# 24V_Multiphase_Buck.net
KiCad netlist of a schematic drawn in Altium Designer
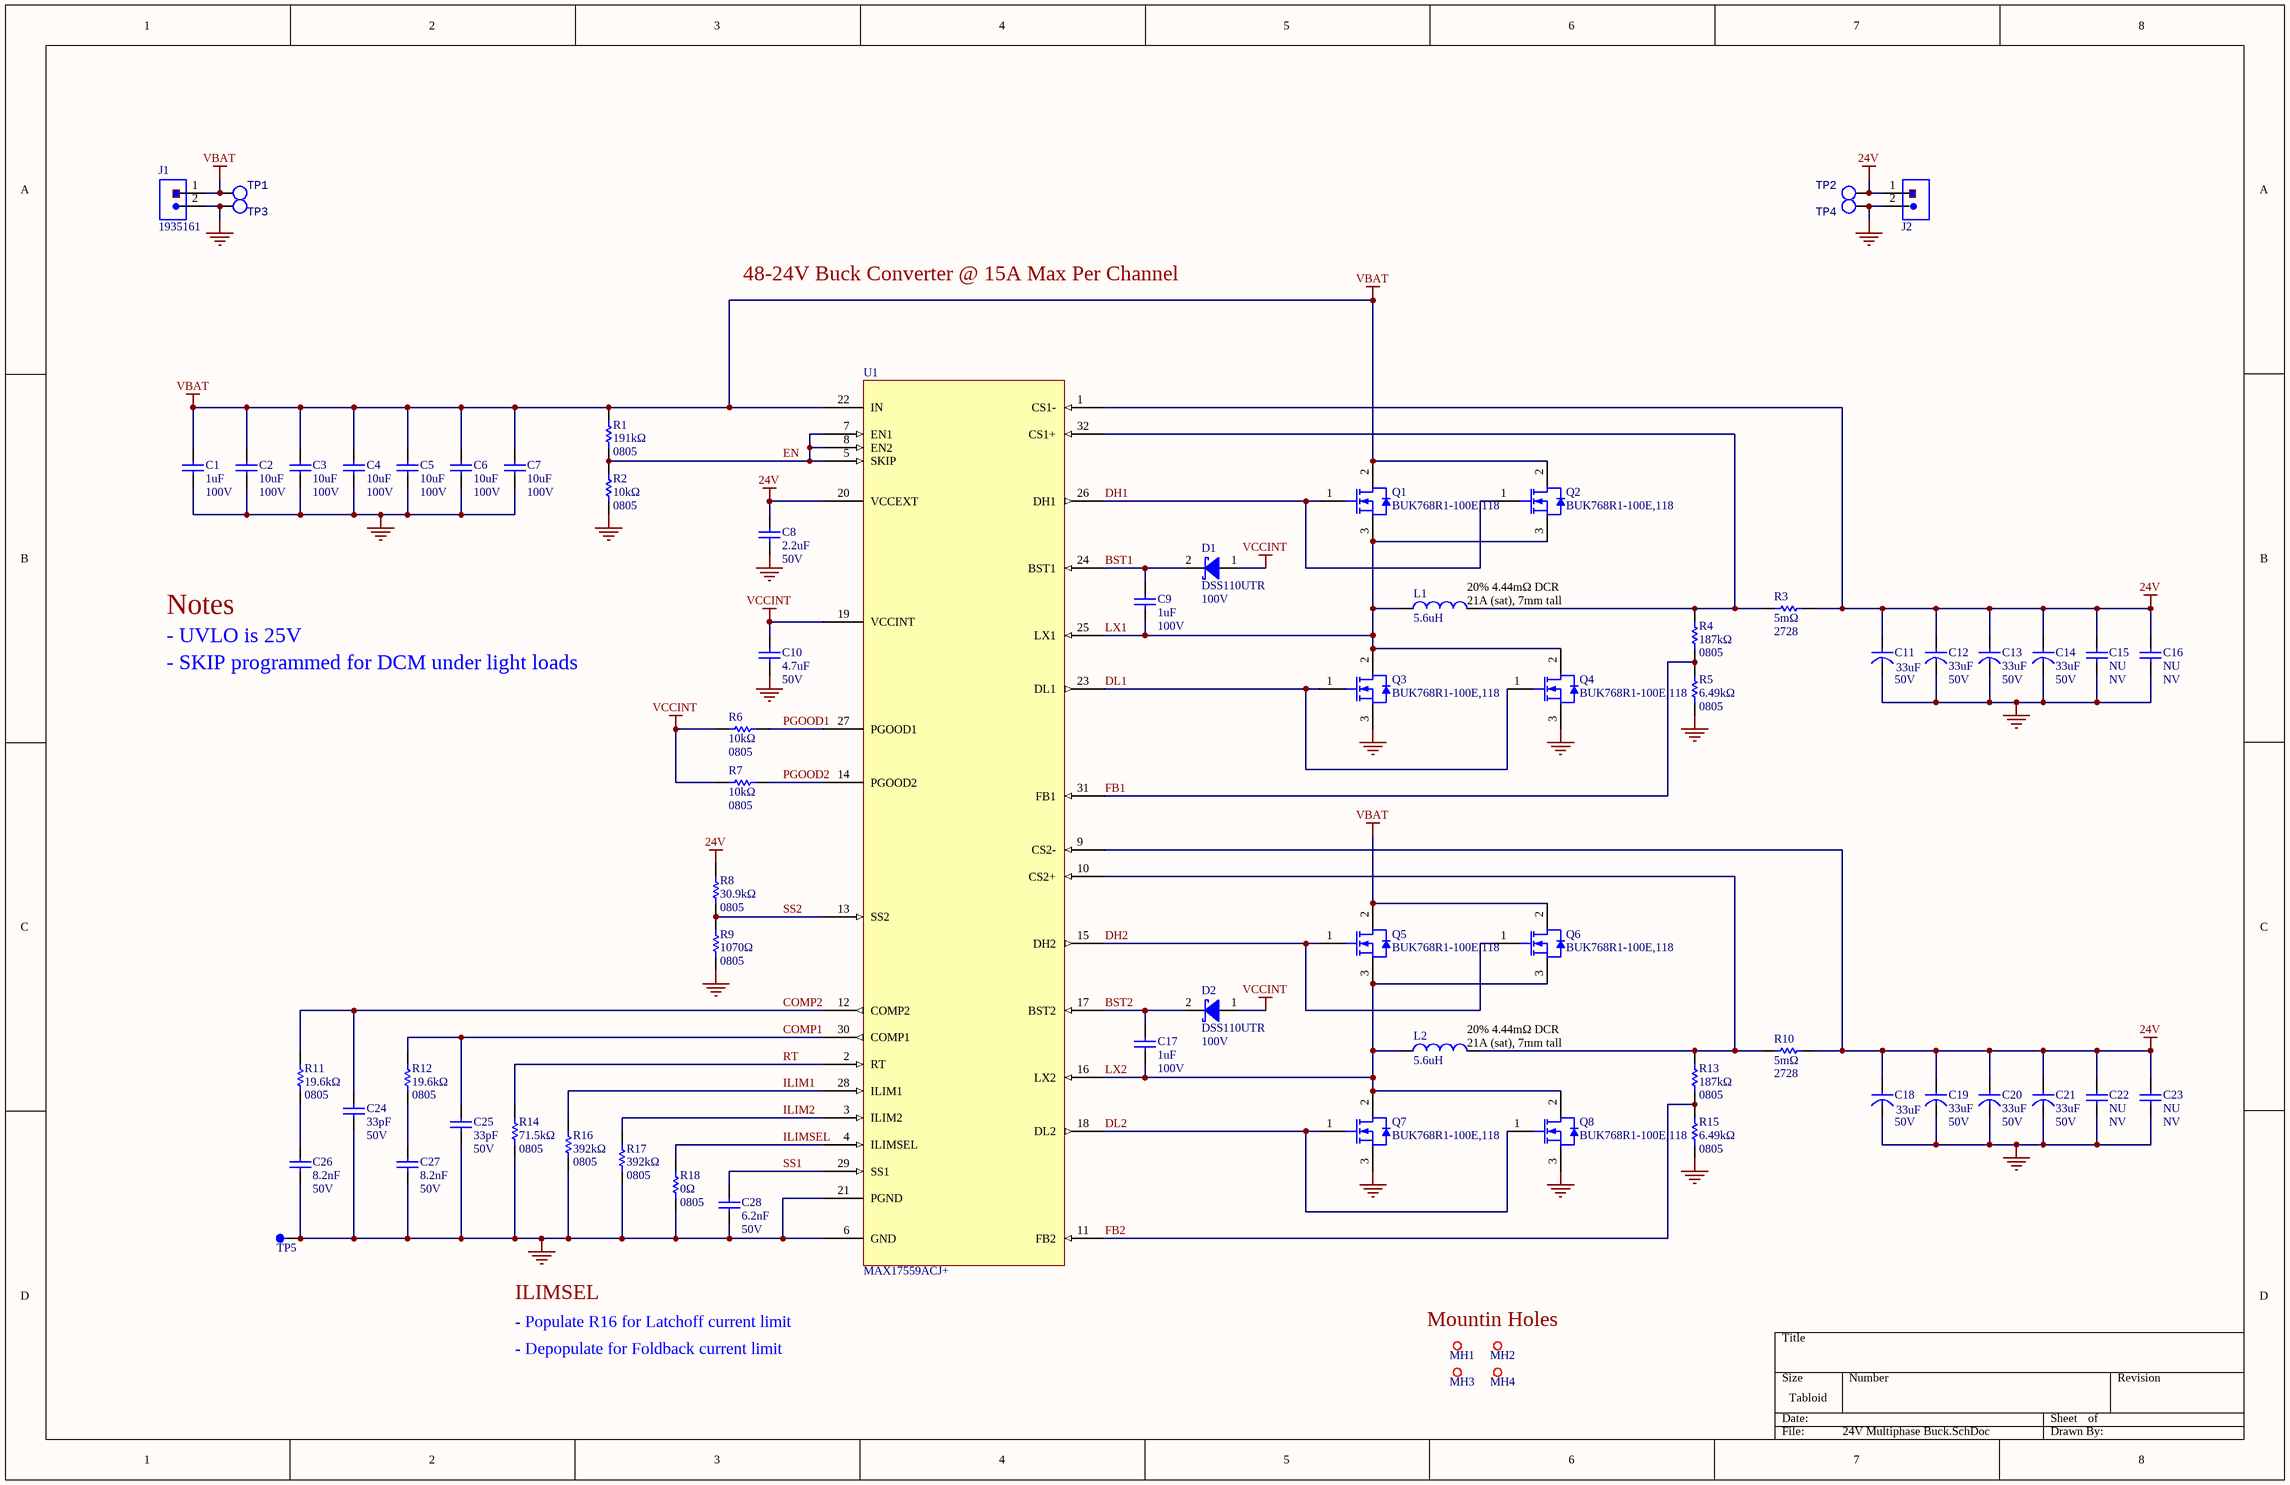
[diagram p0: 24V Multiphase Buck.SchDoc]

(export (version "E")
  (design (tool "Eeschema 10.0.6"))
  (components
    (comp (ref "C1")
      (value "1uF")
      (footprint "C1206")
      (fields
        (field (name "VOLTAGE") "100V")
        (field (name "PART NUMBER") "CL31B105KCHNFNE")
        (field (name "MANUFACTURER") "Samsung Electro-Mechanics")
        (field (name "Comment") "Ceramic Cap")
      )
      (libsource (lib "altium-db-library") (part "Ceramic Cap"))
    )
    (comp (ref "C2")
      (value "10uF")
      (footprint "C2220")
      (fields
        (field (name "VOLTAGE") "100V")
        (field (name "PART NUMBER") "22201C106KAT2A")
        (field (name "MANUFACTURER") "KYOCERA AVX")
        (field (name "Comment") "Ceramic Cap")
      )
      (libsource (lib "altium-db-library") (part "Ceramic Cap"))
    )
    (comp (ref "C3")
      (value "10uF")
      (footprint "C2220")
      (fields
        (field (name "VOLTAGE") "100V")
        (field (name "PART NUMBER") "22201C106KAT2A")
        (field (name "MANUFACTURER") "KYOCERA AVX")
        (field (name "Comment") "Ceramic Cap")
      )
      (libsource (lib "altium-db-library") (part "Ceramic Cap"))
    )
    (comp (ref "C4")
      (value "10uF")
      (footprint "C2220")
      (fields
        (field (name "VOLTAGE") "100V")
        (field (name "PART NUMBER") "22201C106KAT2A")
        (field (name "MANUFACTURER") "KYOCERA AVX")
        (field (name "Comment") "Ceramic Cap")
      )
      (libsource (lib "altium-db-library") (part "Ceramic Cap"))
    )
    (comp (ref "C5")
      (value "10uF")
      (footprint "C2220")
      (fields
        (field (name "VOLTAGE") "100V")
        (field (name "PART NUMBER") "22201C106KAT2A")
        (field (name "MANUFACTURER") "KYOCERA AVX")
        (field (name "Comment") "Ceramic Cap")
      )
      (libsource (lib "altium-db-library") (part "Ceramic Cap"))
    )
    (comp (ref "C6")
      (value "10uF")
      (footprint "C2220")
      (fields
        (field (name "VOLTAGE") "100V")
        (field (name "PART NUMBER") "22201C106KAT2A")
        (field (name "MANUFACTURER") "KYOCERA AVX")
        (field (name "Comment") "Ceramic Cap")
      )
      (libsource (lib "altium-db-library") (part "Ceramic Cap"))
    )
    (comp (ref "C7")
      (value "10uF")
      (footprint "C2220")
      (fields
        (field (name "VOLTAGE") "100V")
        (field (name "PART NUMBER") "22201C106KAT2A")
        (field (name "MANUFACTURER") "KYOCERA AVX")
        (field (name "Comment") "Ceramic Cap")
      )
      (libsource (lib "altium-db-library") (part "Ceramic Cap"))
    )
    (comp (ref "C8")
      (value "2.2uF")
      (footprint "C0805")
      (fields
        (field (name "VOLTAGE") "50V")
        (field (name "PART NUMBER") "CL21A225KBFNNNE")
        (field (name "MANUFACTURER") "Samsung Electro-Mechanics")
        (field (name "Comment") "Ceramic Cap")
      )
      (libsource (lib "altium-db-library") (part "Ceramic Cap"))
    )
    (comp (ref "C9")
      (value "1uF")
      (footprint "C1206")
      (fields
        (field (name "VOLTAGE") "100V")
        (field (name "PART NUMBER") "CL31B105KCHNFNE")
        (field (name "MANUFACTURER") "Samsung Electro-Mechanics")
        (field (name "Comment") "Ceramic Cap")
      )
      (libsource (lib "altium-db-library") (part "Ceramic Cap"))
    )
    (comp (ref "C10")
      (value "4.7uF")
      (footprint "C0805")
      (fields
        (field (name "VOLTAGE") "50V")
        (field (name "PART NUMBER") "GRM21BR61H475KE51L")
        (field (name "MANUFACTURER") "Murata Electronics")
        (field (name "Comment") "Ceramic Cap")
      )
      (libsource (lib "altium-db-library") (part "Ceramic Cap"))
    )
    (comp (ref "C11")
      (value "33uF")
      (footprint "CAPAE9983X105M")
      (fields
        (field (name "VOLTAGE") "50V")
        (field (name "PART NUMBER") "EEV-FC1H330P")
        (field (name "MANUFACTURER") "Panasonic Electronic Components")
        (field (name "Comment") "Electro Cap")
      )
      (libsource (lib "altium-db-library") (part "Electro Cap"))
    )
    (comp (ref "C12")
      (value "33uF")
      (footprint "CAPAE9983X105M")
      (fields
        (field (name "VOLTAGE") "50V")
        (field (name "PART NUMBER") "EEV-FC1H330P")
        (field (name "MANUFACTURER") "Panasonic Electronic Components")
        (field (name "Comment") "Electro Cap")
      )
      (libsource (lib "altium-db-library") (part "Electro Cap"))
    )
    (comp (ref "C13")
      (value "33uF")
      (footprint "CAPAE9983X105M")
      (fields
        (field (name "VOLTAGE") "50V")
        (field (name "PART NUMBER") "EEV-FC1H330P")
        (field (name "MANUFACTURER") "Panasonic Electronic Components")
        (field (name "Comment") "Electro Cap")
      )
      (libsource (lib "altium-db-library") (part "Electro Cap"))
    )
    (comp (ref "C14")
      (value "33uF")
      (footprint "CAPAE9983X105M")
      (fields
        (field (name "VOLTAGE") "50V")
        (field (name "PART NUMBER") "EEV-FC1H330P")
        (field (name "MANUFACTURER") "Panasonic Electronic Components")
        (field (name "Comment") "Electro Cap")
      )
      (libsource (lib "altium-db-library") (part "Electro Cap"))
    )
    (comp (ref "C15")
      (value "NU")
      (footprint "CAPC6153X67N")
      (fields
        (field (name "VOLTAGE") "NV")
        (field (name "PART NUMBER") "KRM55WR71H336MH01K")
        (field (name "MANUFACTURER") "Murata Electronics")
        (field (name "Comment") "Ceramic Cap")
      )
      (libsource (lib "altium-db-library") (part "Ceramic Cap"))
    )
    (comp (ref "C16")
      (value "NU")
      (footprint "CAPC6153X67N")
      (fields
        (field (name "VOLTAGE") "NV")
        (field (name "PART NUMBER") "KRM55WR71H336MH01K")
        (field (name "MANUFACTURER") "Murata Electronics")
        (field (name "Comment") "Ceramic Cap")
      )
      (libsource (lib "altium-db-library") (part "Ceramic Cap"))
    )
    (comp (ref "C17")
      (value "1uF")
      (footprint "C1206")
      (fields
        (field (name "VOLTAGE") "100V")
        (field (name "PART NUMBER") "CL31B105KCHNFNE")
        (field (name "MANUFACTURER") "Samsung Electro-Mechanics")
        (field (name "Comment") "Ceramic Cap")
      )
      (libsource (lib "altium-db-library") (part "Ceramic Cap"))
    )
    (comp (ref "C18")
      (value "33uF")
      (footprint "CAPAE9983X105M")
      (fields
        (field (name "VOLTAGE") "50V")
        (field (name "PART NUMBER") "EEV-FC1H330P")
        (field (name "MANUFACTURER") "Panasonic Electronic Components")
        (field (name "Comment") "Electro Cap")
      )
      (libsource (lib "altium-db-library") (part "Electro Cap"))
    )
    (comp (ref "C19")
      (value "33uF")
      (footprint "CAPAE9983X105M")
      (fields
        (field (name "VOLTAGE") "50V")
        (field (name "PART NUMBER") "EEV-FC1H330P")
        (field (name "MANUFACTURER") "Panasonic Electronic Components")
        (field (name "Comment") "Electro Cap")
      )
      (libsource (lib "altium-db-library") (part "Electro Cap"))
    )
    (comp (ref "C20")
      (value "33uF")
      (footprint "CAPAE9983X105M")
      (fields
        (field (name "VOLTAGE") "50V")
        (field (name "PART NUMBER") "EEV-FC1H330P")
        (field (name "MANUFACTURER") "Panasonic Electronic Components")
        (field (name "Comment") "Electro Cap")
      )
      (libsource (lib "altium-db-library") (part "Electro Cap"))
    )
    (comp (ref "C21")
      (value "33uF")
      (footprint "CAPAE9983X105M")
      (fields
        (field (name "VOLTAGE") "50V")
        (field (name "PART NUMBER") "EEV-FC1H330P")
        (field (name "MANUFACTURER") "Panasonic Electronic Components")
        (field (name "Comment") "Electro Cap")
      )
      (libsource (lib "altium-db-library") (part "Electro Cap"))
    )
    (comp (ref "C22")
      (value "NU")
      (footprint "CAPC6153X67N")
      (fields
        (field (name "VOLTAGE") "NV")
        (field (name "PART NUMBER") "KRM55WR71H336MH01K")
        (field (name "MANUFACTURER") "Murata Electronics")
        (field (name "Comment") "Ceramic Cap")
      )
      (libsource (lib "altium-db-library") (part "Ceramic Cap"))
    )
    (comp (ref "C23")
      (value "NU")
      (footprint "CAPC6153X67N")
      (fields
        (field (name "VOLTAGE") "NV")
        (field (name "PART NUMBER") "KRM55WR71H336MH01K")
        (field (name "MANUFACTURER") "Murata Electronics")
        (field (name "Comment") "Ceramic Cap")
      )
      (libsource (lib "altium-db-library") (part "Ceramic Cap"))
    )
    (comp (ref "C24")
      (value "33pF")
      (footprint "C0805")
      (fields
        (field (name "VOLTAGE") "50V")
        (field (name "PART NUMBER") "C0805C330K5GAC7800")
        (field (name "MANUFACTURER") "KEMET")
        (field (name "Comment") "Ceramic Cap")
      )
      (libsource (lib "altium-db-library") (part "Ceramic Cap"))
    )
    (comp (ref "C25")
      (value "33pF")
      (footprint "C0805")
      (fields
        (field (name "VOLTAGE") "50V")
        (field (name "PART NUMBER") "C0805C330K5GAC7800")
        (field (name "MANUFACTURER") "KEMET")
        (field (name "Comment") "Ceramic Cap")
      )
      (libsource (lib "altium-db-library") (part "Ceramic Cap"))
    )
    (comp (ref "C26")
      (value "8.2nF")
      (footprint "C0805")
      (fields
        (field (name "VOLTAGE") "50V")
        (field (name "PART NUMBER") "CC0805KRX7R9BB822")
        (field (name "MANUFACTURER") "YAGEO")
        (field (name "Comment") "Ceramic Cap")
      )
      (libsource (lib "altium-db-library") (part "Ceramic Cap"))
    )
    (comp (ref "C27")
      (value "8.2nF")
      (footprint "C0805")
      (fields
        (field (name "VOLTAGE") "50V")
        (field (name "PART NUMBER") "CC0805KRX7R9BB822")
        (field (name "MANUFACTURER") "YAGEO")
        (field (name "Comment") "Ceramic Cap")
      )
      (libsource (lib "altium-db-library") (part "Ceramic Cap"))
    )
    (comp (ref "C28")
      (value "6.2nF")
      (footprint "C0805")
      (fields
        (field (name "VOLTAGE") "50V")
        (field (name "PART NUMBER") "GRM2195C1H622JA01D")
        (field (name "MANUFACTURER") "Murata Electronics")
        (field (name "Comment") "Ceramic Cap")
      )
      (libsource (lib "altium-db-library") (part "Ceramic Cap"))
    )
    (comp (ref "D1")
      (value "Schottky Diode")
      (footprint "SODFL360X110-2N")
      (fields
        (field (name "MANUFACTURER PART NUMBER") "DSS110UTR")
        (field (name "VR") "100V")
        (field (name "PART NUMBER") "DSS110UTR")
      )
      (libsource (lib "altium-db-library") (part "Schottky Diode"))
    )
    (comp (ref "D2")
      (value "Schottky Diode")
      (footprint "SODFL360X110-2N")
      (fields
        (field (name "MANUFACTURER PART NUMBER") "DSS110UTR")
        (field (name "VR") "100V")
        (field (name "PART NUMBER") "DSS110UTR")
      )
      (libsource (lib "altium-db-library") (part "Schottky Diode"))
    )
    (comp (ref "J1")
      (value "1935161")
      (footprint "1935161")
      (description "2 Port Terminal")
      (fields (field (name "MANUFACTURER") "Phoenix Contact"))
      (libsource (lib "") (part "1935161_1"))
    )
    (comp (ref "J2")
      (value "1935161")
      (footprint "1935161")
      (fields (field (name "MANUFACTURER") "Phoenix Contact"))
      (libsource (lib "altium-db-library") (part "1935161"))
    )
    (comp (ref "L1")
      (value "5.6uH")
      (footprint "IHLP6767GZER5R6M11")
      (fields
        (field (name "PART NUMBER") "IHLP6767GZER5R6M11")
        (field (name "MANUFACTURER") "Vishay Dale")
        (field (name "TOLERANCE") "20%")
      )
      (libsource (lib "altium-db-library") (part "Inductor"))
    )
    (comp (ref "L2")
      (value "5.6uH")
      (footprint "IHLP6767GZER5R6M11")
      (fields
        (field (name "PART NUMBER") "IHLP6767GZER5R6M11")
        (field (name "MANUFACTURER") "Vishay Dale")
        (field (name "TOLERANCE") "20%")
      )
      (libsource (lib "altium-db-library") (part "Inductor"))
    )
    (comp (ref "MH1")
      (value "MOUNTING_HOLE_M3")
      (footprint "MOUNTING_HOLE_3mm")
      (libsource (lib "UWRT_Schematic_Library_2020") (part "MOUNTING_HOLE_M3"))
    )
    (comp (ref "MH2")
      (value "MOUNTING_HOLE_M3")
      (footprint "MOUNTING_HOLE_3mm")
      (libsource (lib "UWRT_Schematic_Library_2020") (part "MOUNTING_HOLE_M3"))
    )
    (comp (ref "MH3")
      (value "MOUNTING_HOLE_M3")
      (footprint "MOUNTING_HOLE_3mm")
      (libsource (lib "UWRT_Schematic_Library_2020") (part "MOUNTING_HOLE_M3"))
    )
    (comp (ref "MH4")
      (value "MOUNTING_HOLE_M3")
      (footprint "MOUNTING_HOLE_3mm")
      (libsource (lib "UWRT_Schematic_Library_2020") (part "MOUNTING_HOLE_M3"))
    )
    (comp (ref "Q1")
      (value "BUK768R1-100E,118")
      (footprint "DPAK254P1530X450-3N")
      (fields
        (field (name "MANUFACTURER PART NUMBER") "BUK768R1-100E,118")
        (field (name "MANUFACTURER") "Nexperia USA Inc.")
      )
      (libsource (lib "altium-db-library") (part "BUK768R1-100E,118"))
    )
    (comp (ref "Q2")
      (value "BUK768R1-100E,118")
      (footprint "DPAK254P1530X450-3N")
      (fields
        (field (name "MANUFACTURER PART NUMBER") "BUK768R1-100E,118")
        (field (name "MANUFACTURER") "Nexperia USA Inc.")
      )
      (libsource (lib "altium-db-library") (part "BUK768R1-100E,118"))
    )
    (comp (ref "Q3")
      (value "BUK768R1-100E,118")
      (footprint "DPAK254P1530X450-3N")
      (fields
        (field (name "MANUFACTURER PART NUMBER") "BUK768R1-100E,118")
        (field (name "MANUFACTURER") "Nexperia USA Inc.")
      )
      (libsource (lib "altium-db-library") (part "BUK768R1-100E,118"))
    )
    (comp (ref "Q4")
      (value "BUK768R1-100E,118")
      (footprint "DPAK254P1530X450-3N")
      (fields
        (field (name "MANUFACTURER PART NUMBER") "BUK768R1-100E,118")
        (field (name "MANUFACTURER") "Nexperia USA Inc.")
      )
      (libsource (lib "altium-db-library") (part "BUK768R1-100E,118"))
    )
    (comp (ref "Q5")
      (value "BUK768R1-100E,118")
      (footprint "DPAK254P1530X450-3N")
      (fields
        (field (name "MANUFACTURER PART NUMBER") "BUK768R1-100E,118")
        (field (name "MANUFACTURER") "Nexperia USA Inc.")
      )
      (libsource (lib "altium-db-library") (part "BUK768R1-100E,118"))
    )
    (comp (ref "Q6")
      (value "BUK768R1-100E,118")
      (footprint "DPAK254P1530X450-3N")
      (fields
        (field (name "MANUFACTURER PART NUMBER") "BUK768R1-100E,118")
        (field (name "MANUFACTURER") "Nexperia USA Inc.")
      )
      (libsource (lib "altium-db-library") (part "BUK768R1-100E,118"))
    )
    (comp (ref "Q7")
      (value "BUK768R1-100E,118")
      (footprint "DPAK254P1530X450-3N")
      (fields
        (field (name "MANUFACTURER PART NUMBER") "BUK768R1-100E,118")
        (field (name "MANUFACTURER") "Nexperia USA Inc.")
      )
      (libsource (lib "altium-db-library") (part "BUK768R1-100E,118"))
    )
    (comp (ref "Q8")
      (value "BUK768R1-100E,118")
      (footprint "DPAK254P1530X450-3N")
      (fields
        (field (name "MANUFACTURER PART NUMBER") "BUK768R1-100E,118")
        (field (name "MANUFACTURER") "Nexperia USA Inc.")
      )
      (libsource (lib "altium-db-library") (part "BUK768R1-100E,118"))
    )
    (comp (ref "R1")
      (value "191kΩ")
      (footprint "R0805")
      (fields
        (field (name "PACKAGE/FOOTPRINT") "0805")
        (field (name "PART NUMBER") "RC0805FR-07191KL")
        (field (name "MANUFACTURER") "Yageo")
        (field (name "Comment") "Resistor")
      )
      (libsource (lib "altium-db-library") (part "Resistor"))
    )
    (comp (ref "R2")
      (value "10kΩ")
      (footprint "R0805")
      (fields
        (field (name "PACKAGE/FOOTPRINT") "0805")
        (field (name "PART NUMBER") "RC0805JR-0710KL")
        (field (name "MANUFACTURER") "Yageo")
        (field (name "Comment") "Resistor")
      )
      (libsource (lib "altium-db-library") (part "Resistor"))
    )
    (comp (ref "R3")
      (value "5mΩ")
      (footprint "R2728")
      (fields
        (field (name "PACKAGE/FOOTPRINT") "2728")
        (field (name "PART NUMBER") "CSSH2728FT5L00")
        (field (name "MANUFACTURER") "Yageo")
        (field (name "Comment") "Resistor")
      )
      (libsource (lib "altium-db-library") (part "Resistor"))
    )
    (comp (ref "R4")
      (value "187kΩ")
      (footprint "R0805")
      (fields
        (field (name "PACKAGE/FOOTPRINT") "0805")
        (field (name "PART NUMBER") "RT0805BRD07187KL")
        (field (name "MANUFACTURER") "Yageo")
        (field (name "Comment") "Resistor")
      )
      (libsource (lib "altium-db-library") (part "Resistor"))
    )
    (comp (ref "R5")
      (value "6.49kΩ")
      (footprint "R0805")
      (fields
        (field (name "PACKAGE/FOOTPRINT") "0805")
        (field (name "PART NUMBER") "RC0805FR-076K49L")
        (field (name "MANUFACTURER") "Yageo")
        (field (name "Comment") "Resistor")
      )
      (libsource (lib "altium-db-library") (part "Resistor"))
    )
    (comp (ref "R6")
      (value "10kΩ")
      (footprint "R0805")
      (fields
        (field (name "PACKAGE/FOOTPRINT") "0805")
        (field (name "PART NUMBER") "RC0805JR-0710KL")
        (field (name "MANUFACTURER") "Yageo")
        (field (name "Comment") "Resistor")
      )
      (libsource (lib "altium-db-library") (part "Resistor"))
    )
    (comp (ref "R7")
      (value "10kΩ")
      (footprint "R0805")
      (fields
        (field (name "PACKAGE/FOOTPRINT") "0805")
        (field (name "PART NUMBER") "RC0805JR-0710KL")
        (field (name "MANUFACTURER") "Yageo")
        (field (name "Comment") "Resistor")
      )
      (libsource (lib "altium-db-library") (part "Resistor"))
    )
    (comp (ref "R8")
      (value "30.9kΩ")
      (footprint "R0805")
      (fields
        (field (name "PACKAGE/FOOTPRINT") "0805")
        (field (name "PART NUMBER") "RMCF0805FT30K9")
        (field (name "MANUFACTURER") "Stackpole Electronics Inc")
        (field (name "Comment") "Resistor")
      )
      (libsource (lib "altium-db-library") (part "Resistor"))
    )
    (comp (ref "R9")
      (value "1070Ω")
      (footprint "R0805")
      (fields
        (field (name "PACKAGE/FOOTPRINT") "0805")
        (field (name "PART NUMBER") "RC0805FR-071K07L")
        (field (name "MANUFACTURER") "Yageo")
        (field (name "Comment") "Resistor")
      )
      (libsource (lib "altium-db-library") (part "Resistor"))
    )
    (comp (ref "R10")
      (value "5mΩ")
      (footprint "R2728")
      (fields
        (field (name "PACKAGE/FOOTPRINT") "2728")
        (field (name "PART NUMBER") "CSSH2728FT5L00")
        (field (name "MANUFACTURER") "Yageo")
        (field (name "Comment") "Resistor")
      )
      (libsource (lib "altium-db-library") (part "Resistor"))
    )
    (comp (ref "R11")
      (value "19.6kΩ")
      (footprint "R0805")
      (fields
        (field (name "PACKAGE/FOOTPRINT") "0805")
        (field (name "PART NUMBER") "AC0805FR-0719K6L")
        (field (name "MANUFACTURER") "Yageo")
        (field (name "Comment") "Resistor")
      )
      (libsource (lib "altium-db-library") (part "Resistor"))
    )
    (comp (ref "R12")
      (value "19.6kΩ")
      (footprint "R0805")
      (fields
        (field (name "PACKAGE/FOOTPRINT") "0805")
        (field (name "PART NUMBER") "AC0805FR-0719K6L")
        (field (name "MANUFACTURER") "Yageo")
        (field (name "Comment") "Resistor")
      )
      (libsource (lib "altium-db-library") (part "Resistor"))
    )
    (comp (ref "R13")
      (value "187kΩ")
      (footprint "R0805")
      (fields
        (field (name "PACKAGE/FOOTPRINT") "0805")
        (field (name "PART NUMBER") "RT0805BRD07187KL")
        (field (name "MANUFACTURER") "Yageo")
        (field (name "Comment") "Resistor")
      )
      (libsource (lib "altium-db-library") (part "Resistor"))
    )
    (comp (ref "R14")
      (value "71.5kΩ")
      (footprint "R0805")
      (fields
        (field (name "PACKAGE/FOOTPRINT") "0805")
        (field (name "PART NUMBER") "RC0805FR-0771K5L")
        (field (name "MANUFACTURER") "Yageo")
        (field (name "Comment") "Resistor")
      )
      (libsource (lib "altium-db-library") (part "Resistor"))
    )
    (comp (ref "R15")
      (value "6.49kΩ")
      (footprint "R0805")
      (fields
        (field (name "PACKAGE/FOOTPRINT") "0805")
        (field (name "PART NUMBER") "RC0805FR-076K49L")
        (field (name "MANUFACTURER") "Yageo")
        (field (name "Comment") "Resistor")
      )
      (libsource (lib "altium-db-library") (part "Resistor"))
    )
    (comp (ref "R16")
      (value "392kΩ")
      (footprint "R0805")
      (fields
        (field (name "PACKAGE/FOOTPRINT") "0805")
        (field (name "PART NUMBER") "RC0805FR-07392KL")
        (field (name "MANUFACTURER") "Yageo")
        (field (name "Comment") "Resistor")
      )
      (libsource (lib "altium-db-library") (part "Resistor"))
    )
    (comp (ref "R17")
      (value "392kΩ")
      (footprint "R0805")
      (fields
        (field (name "PACKAGE/FOOTPRINT") "0805")
        (field (name "PART NUMBER") "RC0805FR-07392KL")
        (field (name "MANUFACTURER") "Yageo")
        (field (name "Comment") "Resistor")
      )
      (libsource (lib "altium-db-library") (part "Resistor"))
    )
    (comp (ref "R18")
      (value "0Ω")
      (footprint "R0805")
      (fields
        (field (name "PACKAGE/FOOTPRINT") "0805")
        (field (name "PART NUMBER") "RC0805JR-070RL")
        (field (name "MANUFACTURER") "Yageo")
        (field (name "Comment") "Resistor")
      )
      (libsource (lib "altium-db-library") (part "Resistor"))
    )
    (comp (ref "TP1")
      (value "TESTPOINT_LOOP")
      (footprint "TESTPOINT_LOOP")
      (description "TESTPOINT THRUHOLE")
      (libsource (lib "UWRT_Schematic_Library_2020") (part "TESTPOINT_LOOP"))
    )
    (comp (ref "TP2")
      (value "TESTPOINT_LOOP")
      (footprint "TESTPOINT_LOOP")
      (description "TESTPOINT THRUHOLE")
      (libsource (lib "UWRT_Schematic_Library_2020") (part "TESTPOINT_LOOP"))
    )
    (comp (ref "TP3")
      (value "TESTPOINT_LOOP")
      (footprint "TESTPOINT_LOOP")
      (description "TESTPOINT THRUHOLE")
      (libsource (lib "UWRT_Schematic_Library_2020") (part "TESTPOINT_LOOP"))
    )
    (comp (ref "TP4")
      (value "TESTPOINT_LOOP")
      (footprint "TESTPOINT_LOOP")
      (description "TESTPOINT THRUHOLE")
      (libsource (lib "UWRT_Schematic_Library_2020") (part "TESTPOINT_LOOP"))
    )
    (comp (ref "TP5") (value "EMR_TP") (footprint "TP1") (libsource (lib "EMRLibrary") (part "EMR_TP")))
    (comp (ref "U1")
      (value "MAX17559ACJ+")
      (footprint "CQFP80P900X900X120-32N")
      (description "IC REG CTRLR BUCK 32TQFP")
      (fields (field (name "MANUFACTURER") "Maxim"))
      (libsource (lib "EMRLibrary") (part "MAX17559ACJ+"))
    )
  )
  (nets
    (net (code "1") (name "/BST1") (class "Default")
      (node (ref "C9") (pin "2") (pinfunction "2_2") (pintype "passive"))
      (node (ref "D1") (pin "2") (pinfunction "K_2") (pintype "passive"))
      (node (ref "U1") (pin "24") (pinfunction "BST1_24") (pintype "input"))
    )
    (net (code "2") (name "/BST2") (class "Default")
      (node (ref "C17") (pin "2") (pinfunction "2_2") (pintype "passive"))
      (node (ref "D2") (pin "2") (pinfunction "K_2") (pintype "passive"))
      (node (ref "U1") (pin "17") (pinfunction "BST2_17") (pintype "input"))
    )
    (net (code "3") (name "/COMP1") (class "Default")
      (node (ref "C25") (pin "2") (pinfunction "2_2") (pintype "passive"))
      (node (ref "R12") (pin "2") (pinfunction "2_2") (pintype "passive"))
      (node (ref "U1") (pin "30") (pinfunction "COMP1_30") (pintype "output"))
    )
    (net (code "4") (name "/COMP2") (class "Default")
      (node (ref "C24") (pin "2") (pinfunction "2_2") (pintype "passive"))
      (node (ref "R11") (pin "2") (pinfunction "2_2") (pintype "passive"))
      (node (ref "U1") (pin "12") (pinfunction "COMP2_12") (pintype "output"))
    )
    (net (code "5") (name "/DH1") (class "Default")
      (node (ref "Q1") (pin "1") (pinfunction "G_1") (pintype "passive"))
      (node (ref "Q2") (pin "1") (pinfunction "G_1") (pintype "passive"))
      (node (ref "U1") (pin "26") (pinfunction "DH1_26") (pintype "output"))
    )
    (net (code "6") (name "/DH2") (class "Default")
      (node (ref "Q5") (pin "1") (pinfunction "G_1") (pintype "passive"))
      (node (ref "Q6") (pin "1") (pinfunction "G_1") (pintype "passive"))
      (node (ref "U1") (pin "15") (pinfunction "DH2_15") (pintype "output"))
    )
    (net (code "7") (name "/DL1") (class "Default")
      (node (ref "Q3") (pin "1") (pinfunction "G_1") (pintype "passive"))
      (node (ref "Q4") (pin "1") (pinfunction "G_1") (pintype "passive"))
      (node (ref "U1") (pin "23") (pinfunction "DL1_23") (pintype "output"))
    )
    (net (code "8") (name "/DL2") (class "Default")
      (node (ref "Q7") (pin "1") (pinfunction "G_1") (pintype "passive"))
      (node (ref "Q8") (pin "1") (pinfunction "G_1") (pintype "passive"))
      (node (ref "U1") (pin "18") (pinfunction "DL2_18") (pintype "output"))
    )
    (net (code "9") (name "/EN") (class "Default")
      (node (ref "R1") (pin "1") (pinfunction "1_1") (pintype "passive"))
      (node (ref "R2") (pin "2") (pinfunction "2_2") (pintype "passive"))
      (node (ref "U1") (pin "5") (pinfunction "SKIP_5") (pintype "input"))
      (node (ref "U1") (pin "7") (pinfunction "EN1_7") (pintype "input"))
      (node (ref "U1") (pin "8") (pinfunction "EN2_8") (pintype "input"))
    )
    (net (code "10") (name "/FB1") (class "Default")
      (node (ref "R4") (pin "1") (pinfunction "1_1") (pintype "passive"))
      (node (ref "R5") (pin "2") (pinfunction "2_2") (pintype "passive"))
      (node (ref "U1") (pin "31") (pinfunction "FB1_31") (pintype "input"))
    )
    (net (code "11") (name "/FB2") (class "Default")
      (node (ref "R13") (pin "1") (pinfunction "1_1") (pintype "passive"))
      (node (ref "R15") (pin "2") (pinfunction "2_2") (pintype "passive"))
      (node (ref "U1") (pin "11") (pinfunction "FB2_11") (pintype "input"))
    )
    (net (code "12") (name "/ILIM1") (class "Default")
      (node (ref "R16") (pin "2") (pinfunction "2_2") (pintype "passive"))
      (node (ref "U1") (pin "28") (pinfunction "ILIM1_28") (pintype "input"))
    )
    (net (code "13") (name "/ILIM2") (class "Default")
      (node (ref "R17") (pin "2") (pinfunction "2_2") (pintype "passive"))
      (node (ref "U1") (pin "3") (pinfunction "ILIM2_3") (pintype "input"))
    )
    (net (code "14") (name "/ILIMSEL") (class "Default")
      (node (ref "R18") (pin "2") (pinfunction "2_2") (pintype "passive"))
      (node (ref "U1") (pin "4") (pinfunction "ILIMSEL_4") (pintype "input"))
    )
    (net (code "15") (name "/LX1") (class "Default")
      (node (ref "C9") (pin "1") (pinfunction "1_1") (pintype "passive"))
      (node (ref "L1") (pin "1") (pinfunction "1_1") (pintype "passive"))
      (node (ref "Q1") (pin "3") (pinfunction "S_3") (pintype "passive"))
      (node (ref "Q2") (pin "3") (pinfunction "S_3") (pintype "passive"))
      (node (ref "Q3") (pin "2") (pinfunction "D_2") (pintype "passive"))
      (node (ref "Q4") (pin "2") (pinfunction "D_2") (pintype "passive"))
      (node (ref "U1") (pin "25") (pinfunction "LX1_25") (pintype "input"))
    )
    (net (code "16") (name "/LX2") (class "Default")
      (node (ref "C17") (pin "1") (pinfunction "1_1") (pintype "passive"))
      (node (ref "L2") (pin "1") (pinfunction "1_1") (pintype "passive"))
      (node (ref "Q5") (pin "3") (pinfunction "S_3") (pintype "passive"))
      (node (ref "Q6") (pin "3") (pinfunction "S_3") (pintype "passive"))
      (node (ref "Q7") (pin "2") (pinfunction "D_2") (pintype "passive"))
      (node (ref "Q8") (pin "2") (pinfunction "D_2") (pintype "passive"))
      (node (ref "U1") (pin "16") (pinfunction "LX2_16") (pintype "input"))
    )
    (net (code "17") (name "/PGOOD1") (class "Default")
      (node (ref "R6") (pin "2") (pinfunction "2_2") (pintype "passive"))
      (node (ref "U1") (pin "27") (pinfunction "PGOOD1_27") (pintype "open_collector"))
    )
    (net (code "18") (name "/PGOOD2") (class "Default")
      (node (ref "R7") (pin "2") (pinfunction "2_2") (pintype "passive"))
      (node (ref "U1") (pin "14") (pinfunction "PGOOD2_14") (pintype "open_collector"))
    )
    (net (code "19") (name "/RT") (class "Default")
      (node (ref "R14") (pin "2") (pinfunction "2_2") (pintype "passive"))
      (node (ref "U1") (pin "2") (pinfunction "RT_2") (pintype "input"))
    )
    (net (code "20") (name "/SS1") (class "Default")
      (node (ref "C28") (pin "2") (pinfunction "2_2") (pintype "passive"))
      (node (ref "U1") (pin "29") (pinfunction "SS1_29") (pintype "input"))
    )
    (net (code "21") (name "/SS2") (class "Default")
      (node (ref "R8") (pin "1") (pinfunction "1_1") (pintype "passive"))
      (node (ref "R9") (pin "2") (pinfunction "2_2") (pintype "passive"))
      (node (ref "U1") (pin "13") (pinfunction "SS2_13") (pintype "input"))
    )
    (net (code "22") (name "24V") (class "Default")
      (node (ref "C11") (pin "1") (pinfunction "+_1") (pintype "passive"))
      (node (ref "C12") (pin "1") (pinfunction "+_1") (pintype "passive"))
      (node (ref "C13") (pin "1") (pinfunction "+_1") (pintype "passive"))
      (node (ref "C14") (pin "1") (pinfunction "+_1") (pintype "passive"))
      (node (ref "C15") (pin "2") (pinfunction "2_2") (pintype "passive"))
      (node (ref "C16") (pin "2") (pinfunction "2_2") (pintype "passive"))
      (node (ref "C18") (pin "1") (pinfunction "+_1") (pintype "passive"))
      (node (ref "C19") (pin "1") (pinfunction "+_1") (pintype "passive"))
      (node (ref "C20") (pin "1") (pinfunction "+_1") (pintype "passive"))
      (node (ref "C21") (pin "1") (pinfunction "+_1") (pintype "passive"))
      (node (ref "C22") (pin "2") (pinfunction "2_2") (pintype "passive"))
      (node (ref "C23") (pin "2") (pinfunction "2_2") (pintype "passive"))
      (node (ref "C8") (pin "2") (pinfunction "2_2") (pintype "passive"))
      (node (ref "J2") (pin "1") (pintype "passive"))
      (node (ref "R10") (pin "2") (pinfunction "2_2") (pintype "passive"))
      (node (ref "R3") (pin "2") (pinfunction "2_2") (pintype "passive"))
      (node (ref "R8") (pin "2") (pinfunction "2_2") (pintype "passive"))
      (node (ref "TP2") (pin "1") (pintype "passive"))
      (node (ref "U1") (pin "1") (pinfunction "CS1-_1") (pintype "input"))
      (node (ref "U1") (pin "20") (pinfunction "VCCEXT_20") (pintype "power_in"))
      (node (ref "U1") (pin "9") (pinfunction "CS2-_9") (pintype "input"))
    )
    (net (code "23") (name "GND") (class "Default")
      (node (ref "C1") (pin "1") (pinfunction "1_1") (pintype "passive"))
      (node (ref "C10") (pin "1") (pinfunction "1_1") (pintype "passive"))
      (node (ref "C11") (pin "2") (pinfunction "-_2") (pintype "passive"))
      (node (ref "C12") (pin "2") (pinfunction "-_2") (pintype "passive"))
      (node (ref "C13") (pin "2") (pinfunction "-_2") (pintype "passive"))
      (node (ref "C14") (pin "2") (pinfunction "-_2") (pintype "passive"))
      (node (ref "C15") (pin "1") (pinfunction "1_1") (pintype "passive"))
      (node (ref "C16") (pin "1") (pinfunction "1_1") (pintype "passive"))
      (node (ref "C18") (pin "2") (pinfunction "-_2") (pintype "passive"))
      (node (ref "C19") (pin "2") (pinfunction "-_2") (pintype "passive"))
      (node (ref "C2") (pin "1") (pinfunction "1_1") (pintype "passive"))
      (node (ref "C20") (pin "2") (pinfunction "-_2") (pintype "passive"))
      (node (ref "C21") (pin "2") (pinfunction "-_2") (pintype "passive"))
      (node (ref "C22") (pin "1") (pinfunction "1_1") (pintype "passive"))
      (node (ref "C23") (pin "1") (pinfunction "1_1") (pintype "passive"))
      (node (ref "C24") (pin "1") (pinfunction "1_1") (pintype "passive"))
      (node (ref "C25") (pin "1") (pinfunction "1_1") (pintype "passive"))
      (node (ref "C26") (pin "1") (pinfunction "1_1") (pintype "passive"))
      (node (ref "C27") (pin "1") (pinfunction "1_1") (pintype "passive"))
      (node (ref "C28") (pin "1") (pinfunction "1_1") (pintype "passive"))
      (node (ref "C3") (pin "1") (pinfunction "1_1") (pintype "passive"))
      (node (ref "C4") (pin "1") (pinfunction "1_1") (pintype "passive"))
      (node (ref "C5") (pin "1") (pinfunction "1_1") (pintype "passive"))
      (node (ref "C6") (pin "1") (pinfunction "1_1") (pintype "passive"))
      (node (ref "C7") (pin "1") (pinfunction "1_1") (pintype "passive"))
      (node (ref "C8") (pin "1") (pinfunction "1_1") (pintype "passive"))
      (node (ref "J1") (pin "2") (pintype "passive"))
      (node (ref "J2") (pin "2") (pintype "passive"))
      (node (ref "Q3") (pin "3") (pinfunction "S_3") (pintype "passive"))
      (node (ref "Q4") (pin "3") (pinfunction "S_3") (pintype "passive"))
      (node (ref "Q7") (pin "3") (pinfunction "S_3") (pintype "passive"))
      (node (ref "Q8") (pin "3") (pinfunction "S_3") (pintype "passive"))
      (node (ref "R14") (pin "1") (pinfunction "1_1") (pintype "passive"))
      (node (ref "R15") (pin "1") (pinfunction "1_1") (pintype "passive"))
      (node (ref "R16") (pin "1") (pinfunction "1_1") (pintype "passive"))
      (node (ref "R17") (pin "1") (pinfunction "1_1") (pintype "passive"))
      (node (ref "R18") (pin "1") (pinfunction "1_1") (pintype "passive"))
      (node (ref "R2") (pin "1") (pinfunction "1_1") (pintype "passive"))
      (node (ref "R5") (pin "1") (pinfunction "1_1") (pintype "passive"))
      (node (ref "R9") (pin "1") (pinfunction "1_1") (pintype "passive"))
      (node (ref "TP3") (pin "1") (pintype "passive"))
      (node (ref "TP4") (pin "1") (pintype "passive"))
      (node (ref "TP5") (pin "1") (pinfunction "A_1") (pintype "passive"))
      (node (ref "U1") (pin "21") (pinfunction "PGND_21") (pintype "power_in"))
      (node (ref "U1") (pin "6") (pinfunction "GND_6") (pintype "power_in"))
    )
    (net (code "24") (name "Net-(C26-Pad2)") (class "Default")
      (node (ref "C26") (pin "2") (pinfunction "2_2") (pintype "passive"))
      (node (ref "R11") (pin "1") (pinfunction "1_1") (pintype "passive"))
    )
    (net (code "25") (name "Net-(C27-Pad2)") (class "Default")
      (node (ref "C27") (pin "2") (pinfunction "2_2") (pintype "passive"))
      (node (ref "R12") (pin "1") (pinfunction "1_1") (pintype "passive"))
    )
    (net (code "26") (name "Net-(U1-CS1+)") (class "Default")
      (node (ref "L1") (pin "2") (pinfunction "2_2") (pintype "passive"))
      (node (ref "R3") (pin "1") (pinfunction "1_1") (pintype "passive"))
      (node (ref "R4") (pin "2") (pinfunction "2_2") (pintype "passive"))
      (node (ref "U1") (pin "32") (pinfunction "CS1+_32") (pintype "input"))
    )
    (net (code "27") (name "Net-(U1-CS2+)") (class "Default")
      (node (ref "L2") (pin "2") (pinfunction "2_2") (pintype "passive"))
      (node (ref "R10") (pin "1") (pinfunction "1_1") (pintype "passive"))
      (node (ref "R13") (pin "2") (pinfunction "2_2") (pintype "passive"))
      (node (ref "U1") (pin "10") (pinfunction "CS2+_10") (pintype "input"))
    )
    (net (code "28") (name "VBAT") (class "Default")
      (node (ref "C1") (pin "2") (pinfunction "2_2") (pintype "passive"))
      (node (ref "C2") (pin "2") (pinfunction "2_2") (pintype "passive"))
      (node (ref "C3") (pin "2") (pinfunction "2_2") (pintype "passive"))
      (node (ref "C4") (pin "2") (pinfunction "2_2") (pintype "passive"))
      (node (ref "C5") (pin "2") (pinfunction "2_2") (pintype "passive"))
      (node (ref "C6") (pin "2") (pinfunction "2_2") (pintype "passive"))
      (node (ref "C7") (pin "2") (pinfunction "2_2") (pintype "passive"))
      (node (ref "J1") (pin "1") (pintype "passive"))
      (node (ref "Q1") (pin "2") (pinfunction "D_2") (pintype "passive"))
      (node (ref "Q2") (pin "2") (pinfunction "D_2") (pintype "passive"))
      (node (ref "Q5") (pin "2") (pinfunction "D_2") (pintype "passive"))
      (node (ref "Q6") (pin "2") (pinfunction "D_2") (pintype "passive"))
      (node (ref "R1") (pin "2") (pinfunction "2_2") (pintype "passive"))
      (node (ref "TP1") (pin "1") (pintype "passive"))
      (node (ref "U1") (pin "22") (pinfunction "IN_22") (pintype "power_in"))
    )
    (net (code "29") (name "VCCINT") (class "Default")
      (node (ref "C10") (pin "2") (pinfunction "2_2") (pintype "passive"))
      (node (ref "D1") (pin "1") (pinfunction "A_1") (pintype "passive"))
      (node (ref "D2") (pin "1") (pinfunction "A_1") (pintype "passive"))
      (node (ref "R6") (pin "1") (pinfunction "1_1") (pintype "passive"))
      (node (ref "R7") (pin "1") (pinfunction "1_1") (pintype "passive"))
      (node (ref "U1") (pin "19") (pinfunction "VCCINT_19") (pintype "power_in"))
    )
  )
)
